# oled.net
KiCad netlist of a schematic drawn in Altium Designer
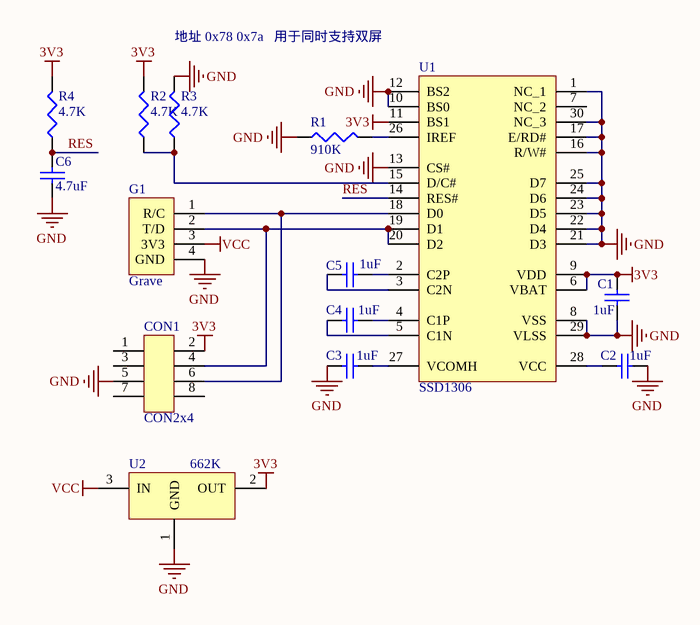
[diagram p0: oled.SchDoc]

(export (version "E")
  (design (tool "Eeschema 10.0.6"))
  (components
    (comp (ref "C1")
      (value "1uF")
      (footprint "0603_C")
      (fields (field (name "PUBLISHER") "Altium Limited"))
      (libsource (lib "misc") (part "Cap"))
    )
    (comp (ref "C2")
      (value "1uF")
      (footprint "0603_C")
      (fields (field (name "PUBLISHER") "Altium Limited"))
      (libsource (lib "misc") (part "Cap"))
    )
    (comp (ref "C3")
      (value "1uF")
      (footprint "0603_C")
      (fields (field (name "PUBLISHER") "Altium Limited"))
      (libsource (lib "misc") (part "Cap"))
    )
    (comp (ref "C4")
      (value "1uF")
      (footprint "0603_C")
      (fields (field (name "PUBLISHER") "Altium Limited"))
      (libsource (lib "misc") (part "Cap"))
    )
    (comp (ref "C5")
      (value "1uF")
      (footprint "0603_C")
      (fields (field (name "PUBLISHER") "Altium Limited"))
      (libsource (lib "misc") (part "Cap"))
    )
    (comp (ref "C6")
      (value "4.7uF")
      (footprint "0603_C")
      (fields (field (name "PUBLISHER") "Altium Limited"))
      (libsource (lib "misc") (part "Cap"))
    )
    (comp (ref "CON1")
      (value "CON2x4")
      (footprint "2x4P_SMT_2.54mm")
      (libsource (lib "misc") (part "CON2x4"))
    )
    (comp (ref "G1") (value "Grave") (footprint "S4B-PH-SM4") (libsource (lib "misc") (part "Grove")))
    (comp (ref "R1")
      (value "910K")
      (footprint "0603_R")
      (fields (field (name "PUBLISHER") "Altium Limited"))
      (libsource (lib "misc") (part "Res"))
    )
    (comp (ref "R2")
      (value "4.7K")
      (footprint "0603_R")
      (fields (field (name "PUBLISHER") "Altium Limited"))
      (libsource (lib "misc") (part "Res"))
    )
    (comp (ref "R3")
      (value "4.7K")
      (footprint "0603_R")
      (fields (field (name "PUBLISHER") "Altium Limited"))
      (libsource (lib "misc") (part "Res"))
    )
    (comp (ref "R4")
      (value "4.7K")
      (footprint "0603_R")
      (fields (field (name "PUBLISHER") "Altium Limited"))
      (libsource (lib "misc") (part "Res"))
    )
    (comp (ref "U1") (value "SSD1306") (footprint "OLED-0.96-30") (libsource (lib "misc1") (part "SSD1306")))
    (comp (ref "U2")
      (value "662K")
      (footprint "SOT23-3")
      (description "或 S-1206B30-M3")
      (libsource (lib "misc") (part "662K"))
    )
  )
  (nets
    (net (code "1") (name "/RES") (class "Default")
      (node (ref "C6") (pin "2") (pinfunction "2_2") (pintype "passive"))
      (node (ref "R4") (pin "1") (pinfunction "1_1") (pintype "passive"))
      (node (ref "U1") (pin "14") (pinfunction "RES#_14") (pintype "passive"))
    )
    (net (code "2") (name "3V3") (class "Default")
      (node (ref "C1") (pin "2") (pinfunction "2_2") (pintype "passive"))
      (node (ref "CON1") (pin "2") (pintype "passive"))
      (node (ref "R2") (pin "2") (pinfunction "2_2") (pintype "passive"))
      (node (ref "R4") (pin "2") (pinfunction "2_2") (pintype "passive"))
      (node (ref "U1") (pin "11") (pinfunction "BS1_11") (pintype "passive"))
      (node (ref "U1") (pin "6") (pinfunction "VBAT_6") (pintype "passive"))
      (node (ref "U1") (pin "9") (pinfunction "VDD_9") (pintype "passive"))
      (node (ref "U2") (pin "2") (pinfunction "OUT_2") (pintype "passive"))
    )
    (net (code "3") (name "GND") (class "Default")
      (node (ref "C1") (pin "1") (pinfunction "1_1") (pintype "passive"))
      (node (ref "C2") (pin "2") (pinfunction "2_2") (pintype "passive"))
      (node (ref "C3") (pin "1") (pinfunction "1_1") (pintype "passive"))
      (node (ref "C6") (pin "1") (pinfunction "1_1") (pintype "passive"))
      (node (ref "CON1") (pin "5") (pintype "passive"))
      (node (ref "G1") (pin "4") (pinfunction "GND_4") (pintype "passive"))
      (node (ref "R1") (pin "1") (pinfunction "1_1") (pintype "passive"))
      (node (ref "R3") (pin "2") (pinfunction "2_2") (pintype "passive"))
      (node (ref "U1") (pin "1") (pinfunction "NC_1_1") (pintype "passive"))
      (node (ref "U1") (pin "10") (pinfunction "BS0_10") (pintype "passive"))
      (node (ref "U1") (pin "12") (pinfunction "BS2_12") (pintype "passive"))
      (node (ref "U1") (pin "13") (pinfunction "CS#_13") (pintype "passive"))
      (node (ref "U1") (pin "16") (pinfunction "R/W#_16") (pintype "passive"))
      (node (ref "U1") (pin "17") (pinfunction "E/RD#_17") (pintype "passive"))
      (node (ref "U1") (pin "21") (pinfunction "D3_21") (pintype "passive"))
      (node (ref "U1") (pin "22") (pinfunction "D4_22") (pintype "passive"))
      (node (ref "U1") (pin "23") (pinfunction "D5_23") (pintype "passive"))
      (node (ref "U1") (pin "24") (pinfunction "D6_24") (pintype "passive"))
      (node (ref "U1") (pin "25") (pinfunction "D7_25") (pintype "passive"))
      (node (ref "U1") (pin "29") (pinfunction "VLSS_29") (pintype "passive"))
      (node (ref "U1") (pin "30") (pinfunction "NC_3_30") (pintype "passive"))
      (node (ref "U1") (pin "8") (pinfunction "VSS_8") (pintype "passive"))
      (node (ref "U2") (pin "1") (pinfunction "GND_1") (pintype "passive"))
    )
    (net (code "4") (name "Net-(G1-R{slash}C)") (class "Default")
      (node (ref "CON1") (pin "6") (pintype "passive"))
      (node (ref "G1") (pin "1") (pinfunction "R/C_1") (pintype "passive"))
      (node (ref "U1") (pin "18") (pinfunction "D0_18") (pintype "passive"))
    )
    (net (code "5") (name "Net-(G1-T{slash}D)") (class "Default")
      (node (ref "CON1") (pin "4") (pintype "passive"))
      (node (ref "G1") (pin "2") (pinfunction "T/D_2") (pintype "passive"))
      (node (ref "U1") (pin "19") (pinfunction "D1_19") (pintype "passive"))
      (node (ref "U1") (pin "20") (pinfunction "D2_20") (pintype "passive"))
    )
    (net (code "6") (name "Net-(U1-C1N)") (class "Default")
      (node (ref "C4") (pin "1") (pinfunction "1_1") (pintype "passive"))
      (node (ref "U1") (pin "5") (pinfunction "C1N_5") (pintype "passive"))
    )
    (net (code "7") (name "Net-(U1-C1P)") (class "Default")
      (node (ref "C4") (pin "2") (pinfunction "2_2") (pintype "passive"))
      (node (ref "U1") (pin "4") (pinfunction "C1P_4") (pintype "passive"))
    )
    (net (code "8") (name "Net-(U1-C2N)") (class "Default")
      (node (ref "C5") (pin "1") (pinfunction "1_1") (pintype "passive"))
      (node (ref "U1") (pin "3") (pinfunction "C2N_3") (pintype "passive"))
    )
    (net (code "9") (name "Net-(U1-C2P)") (class "Default")
      (node (ref "C5") (pin "2") (pinfunction "2_2") (pintype "passive"))
      (node (ref "U1") (pin "2") (pinfunction "C2P_2") (pintype "passive"))
    )
    (net (code "10") (name "Net-(U1-D{slash}C#)") (class "Default")
      (node (ref "R2") (pin "1") (pinfunction "1_1") (pintype "passive"))
      (node (ref "R3") (pin "1") (pinfunction "1_1") (pintype "passive"))
      (node (ref "U1") (pin "15") (pinfunction "D/C#_15") (pintype "passive"))
    )
    (net (code "11") (name "Net-(U1-IREF)") (class "Default")
      (node (ref "R1") (pin "2") (pinfunction "2_2") (pintype "passive"))
      (node (ref "U1") (pin "26") (pinfunction "IREF_26") (pintype "passive"))
    )
    (net (code "12") (name "Net-(U1-VCC)") (class "Default")
      (node (ref "C2") (pin "1") (pinfunction "1_1") (pintype "passive"))
      (node (ref "U1") (pin "28") (pinfunction "VCC_28") (pintype "passive"))
    )
    (net (code "13") (name "Net-(U1-VCOMH)") (class "Default")
      (node (ref "C3") (pin "2") (pinfunction "2_2") (pintype "passive"))
      (node (ref "U1") (pin "27") (pinfunction "VCOMH_27") (pintype "passive"))
    )
    (net (code "14") (name "VCC") (class "Default")
      (node (ref "G1") (pin "3") (pinfunction "3V3_3") (pintype "passive"))
      (node (ref "U2") (pin "3") (pinfunction "IN_3") (pintype "passive"))
    )
    (net (code "15") (name "unconnected-(CON1-Pad1)") (class "Default")
      (node (ref "CON1") (pin "1") (pintype "passive"))
    )
    (net (code "16") (name "unconnected-(CON1-Pad3)") (class "Default")
      (node (ref "CON1") (pin "3") (pintype "passive"))
    )
    (net (code "17") (name "unconnected-(CON1-Pad7)") (class "Default")
      (node (ref "CON1") (pin "7") (pintype "passive"))
    )
    (net (code "18") (name "unconnected-(CON1-Pad8)") (class "Default")
      (node (ref "CON1") (pin "8") (pintype "passive"))
    )
    (net (code "19") (name "unconnected-(U1-NC_2-Pad7)") (class "Default")
      (node (ref "U1") (pin "7") (pinfunction "NC_2_7") (pintype "passive"))
    )
  )
)
